# baseControl2.net
KiCad netlist of a schematic drawn in Altium Designer
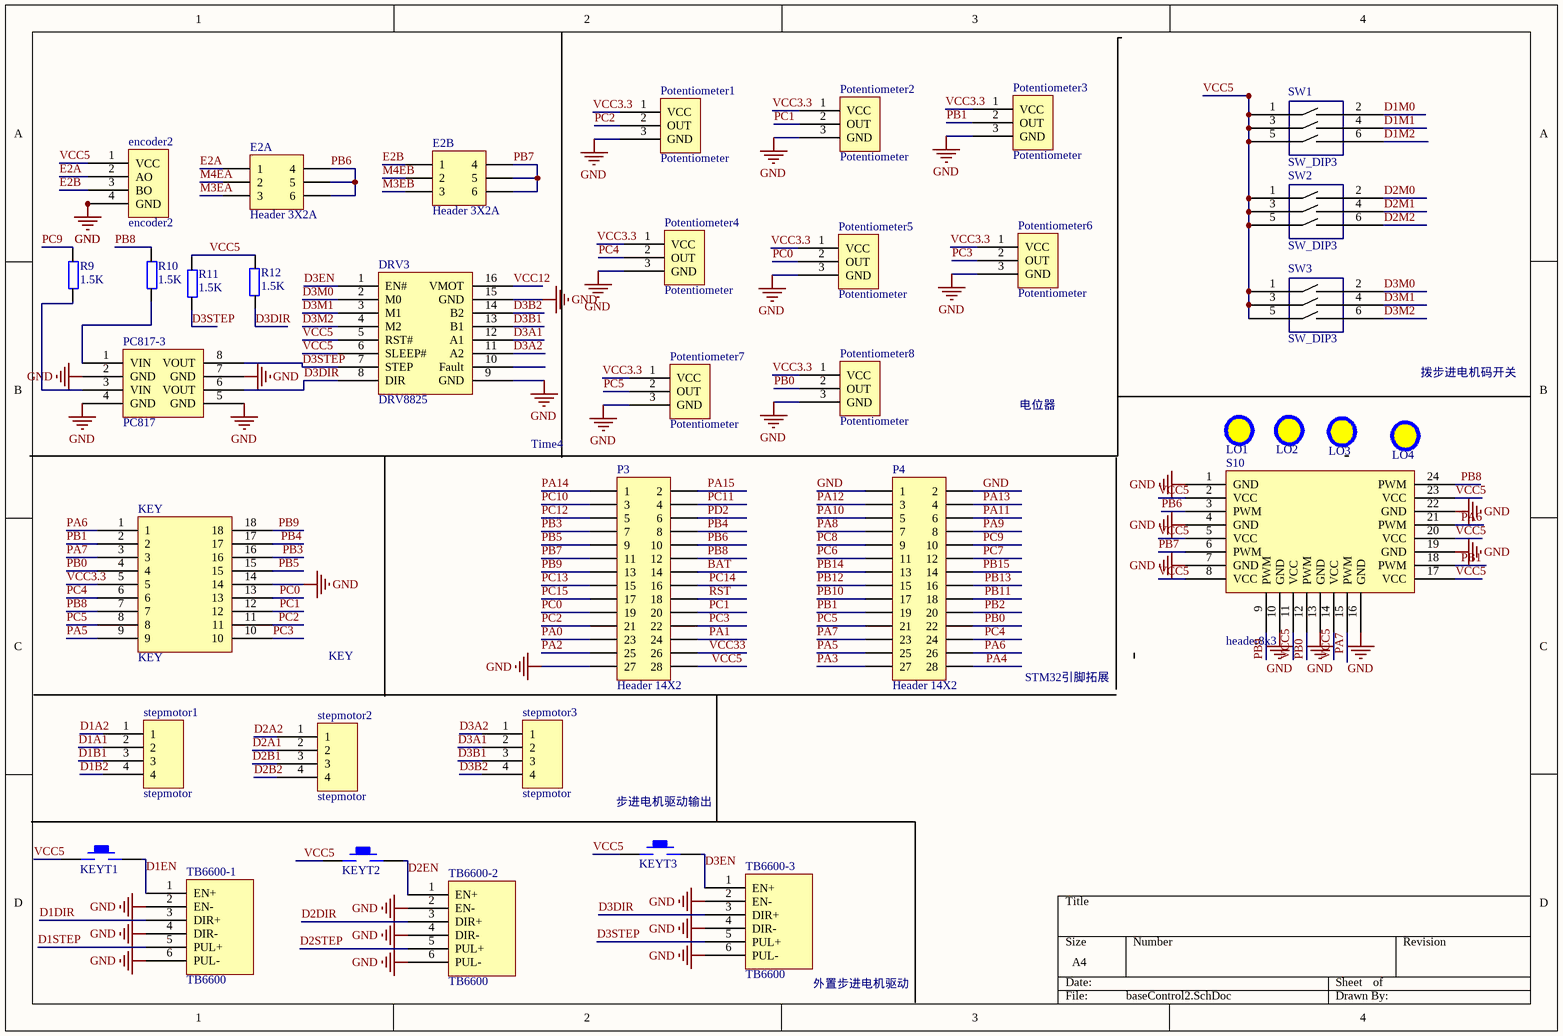
[diagram p0: baseControl2.SchDoc]

(export (version "E")
  (design (tool "Eeschema 10.0.6"))
  (components
    (comp (ref "DRV3")
      (value "DRV8825")
      (footprint "DRV8825")
      (libsource (lib "controlBsae") (part "DRV8825"))
    )
    (comp (ref "E2A")
      (value "Header 3X2A")
      (footprint "HDR2X3_CEN")
      (description "Header, 3-Pin, Dual row")
      (fields (field (name "PUBLISHER") "Altium Limited"))
      (libsource (lib "Miscellaneous Connectors") (part "Header 3X2A"))
    )
    (comp (ref "E2B")
      (value "Header 3X2A")
      (footprint "HDR2X3_CEN")
      (description "Header, 3-Pin, Dual row")
      (fields (field (name "PUBLISHER") "Altium Limited"))
      (libsource (lib "Miscellaneous Connectors") (part "Header 3X2A"))
    )
    (comp (ref "encoder2")
      (value "encoder2")
      (footprint "XH-4-254")
      (libsource (lib "controlBsae") (part "encoder"))
    )
    (comp (ref "KEY") (value "KEY") (footprint "KEY") (libsource (lib "controlBsae") (part "KEY")))
    (comp (ref "KEYT1") (value "KEY") (footprint "KEY_M") (libsource (lib "CORE") (part "KEY")))
    (comp (ref "KEYT2") (value "KEY") (footprint "KEY_M") (libsource (lib "CORE") (part "KEY")))
    (comp (ref "KEYT3") (value "KEY") (footprint "KEY_M") (libsource (lib "CORE") (part "KEY")))
    (comp (ref "LO1") (value "螺丝孔") (footprint "VIA") (libsource (lib "CORE") (part "螺丝孔")))
    (comp (ref "LO2") (value "螺丝孔") (footprint "VIA") (libsource (lib "CORE") (part "螺丝孔")))
    (comp (ref "LO3") (value "螺丝孔") (footprint "VIA") (libsource (lib "CORE") (part "螺丝孔")))
    (comp (ref "LO4") (value "螺丝孔") (footprint "VIA") (libsource (lib "CORE") (part "螺丝孔")))
    (comp (ref "P3")
      (value "Header 14X2")
      (footprint "HDR2X14")
      (description "Header, 14-Pin, Dual row")
      (fields (field (name "PUBLISHER") "Altium Limited"))
      (libsource (lib "Miscellaneous Connectors") (part "Header 14X2"))
    )
    (comp (ref "P4")
      (value "Header 14X2")
      (footprint "HDR2X14")
      (description "Header, 14-Pin, Dual row")
      (fields (field (name "PUBLISHER") "Altium Limited"))
      (libsource (lib "Miscellaneous Connectors") (part "Header 14X2"))
    )
    (comp (ref "PC817-3") (value "PC817") (footprint "DIP4") (libsource (lib "controlBsae") (part "PC817")))
    (comp (ref "Potentiometer1")
      (value "Potentiometer")
      (footprint "Potentiometer")
      (libsource (lib "controlBsae") (part "Potentiometer"))
    )
    (comp (ref "Potentiometer2")
      (value "Potentiometer")
      (footprint "Potentiometer")
      (libsource (lib "controlBsae") (part "Potentiometer"))
    )
    (comp (ref "Potentiometer3")
      (value "Potentiometer")
      (footprint "Potentiometer")
      (libsource (lib "controlBsae") (part "Potentiometer"))
    )
    (comp (ref "Potentiometer4")
      (value "Potentiometer")
      (footprint "Potentiometer")
      (libsource (lib "controlBsae") (part "Potentiometer"))
    )
    (comp (ref "Potentiometer5")
      (value "Potentiometer")
      (footprint "Potentiometer")
      (libsource (lib "controlBsae") (part "Potentiometer"))
    )
    (comp (ref "Potentiometer6")
      (value "Potentiometer")
      (footprint "Potentiometer")
      (libsource (lib "controlBsae") (part "Potentiometer"))
    )
    (comp (ref "Potentiometer7")
      (value "Potentiometer")
      (footprint "Potentiometer")
      (libsource (lib "controlBsae") (part "Potentiometer"))
    )
    (comp (ref "Potentiometer8")
      (value "Potentiometer")
      (footprint "Potentiometer")
      (libsource (lib "controlBsae") (part "Potentiometer"))
    )
    (comp (ref "R9") (value "1.5K") (footprint "0603P") (libsource (lib "CORE") (part "R")))
    (comp (ref "R10") (value "1.5K") (footprint "0603P") (libsource (lib "CORE") (part "R")))
    (comp (ref "R11") (value "1.5K") (footprint "0603P") (libsource (lib "CORE") (part "R")))
    (comp (ref "R12") (value "1.5K") (footprint "0603P") (libsource (lib "CORE") (part "R")))
    (comp (ref "S10")
      (value "header8x3")
      (footprint "header8X3")
      (libsource (lib "baseControl") (part "header8x3"))
    )
    (comp (ref "stepmotor1")
      (value "stepmotor")
      (footprint "XH-4-254")
      (libsource (lib "controlBsae") (part "stepmotor"))
    )
    (comp (ref "stepmotor2")
      (value "stepmotor")
      (footprint "XH-4-254")
      (libsource (lib "controlBsae") (part "stepmotor"))
    )
    (comp (ref "stepmotor3")
      (value "stepmotor")
      (footprint "XH-4-254")
      (libsource (lib "controlBsae") (part "stepmotor"))
    )
    (comp (ref "SW1")
      (value "SW_DIP3")
      (footprint "SW_DIP3")
      (libsource (lib "controlBsae") (part "SW_DIP3"))
    )
    (comp (ref "SW2")
      (value "SW_DIP3")
      (footprint "SW_DIP3")
      (libsource (lib "controlBsae") (part "SW_DIP3"))
    )
    (comp (ref "SW3")
      (value "SW_DIP3")
      (footprint "SW_DIP3")
      (libsource (lib "controlBsae") (part "SW_DIP3"))
    )
    (comp (ref "TB6600-1")
      (value "TB6600")
      (footprint "XH-6-254")
      (libsource (lib "controlBsae") (part "TB6600"))
    )
    (comp (ref "TB6600-2")
      (value "TB6600")
      (footprint "XH-6-254")
      (libsource (lib "controlBsae") (part "TB6600"))
    )
    (comp (ref "TB6600-3")
      (value "TB6600")
      (footprint "XH-6-254")
      (libsource (lib "controlBsae") (part "TB6600"))
    )
  )
  (nets
    (net (code "1") (name "/BAT") (class "Default")
      (node (ref "P3") (pin "14") (pinfunction "14_14") (pintype "passive"))
    )
    (net (code "2") (name "/D1A1") (class "Default")
      (node (ref "stepmotor1") (pin "2") (pinfunction "2_2") (pintype "passive"))
    )
    (net (code "3") (name "/D1A2") (class "Default")
      (node (ref "stepmotor1") (pin "1") (pinfunction "1_1") (pintype "passive"))
    )
    (net (code "4") (name "/D1B1") (class "Default")
      (node (ref "stepmotor1") (pin "3") (pinfunction "3_3") (pintype "passive"))
    )
    (net (code "5") (name "/D1B2") (class "Default")
      (node (ref "stepmotor1") (pin "4") (pinfunction "4_4") (pintype "passive"))
    )
    (net (code "6") (name "/D1DIR") (class "Default")
      (node (ref "TB6600-1") (pin "3") (pinfunction "DIR+_3") (pintype "passive"))
    )
    (net (code "7") (name "/D1EN") (class "Default")
      (node (ref "KEYT1") (pin "2") (pinfunction "2_2") (pintype "passive"))
      (node (ref "TB6600-1") (pin "1") (pinfunction "EN+_1") (pintype "passive"))
    )
    (net (code "8") (name "/D1M0") (class "Default")
      (node (ref "SW1") (pin "2") (pinfunction "2_2") (pintype "passive"))
    )
    (net (code "9") (name "/D1M1") (class "Default")
      (node (ref "SW1") (pin "4") (pinfunction "4_4") (pintype "passive"))
    )
    (net (code "10") (name "/D1M2") (class "Default")
      (node (ref "SW1") (pin "6") (pinfunction "6_6") (pintype "passive"))
    )
    (net (code "11") (name "/D1STEP") (class "Default")
      (node (ref "TB6600-1") (pin "5") (pinfunction "PUL+_5") (pintype "passive"))
    )
    (net (code "12") (name "/D2A1") (class "Default")
      (node (ref "stepmotor2") (pin "2") (pinfunction "2_2") (pintype "passive"))
    )
    (net (code "13") (name "/D2A2") (class "Default")
      (node (ref "stepmotor2") (pin "1") (pinfunction "1_1") (pintype "passive"))
    )
    (net (code "14") (name "/D2B1") (class "Default")
      (node (ref "stepmotor2") (pin "3") (pinfunction "3_3") (pintype "passive"))
    )
    (net (code "15") (name "/D2B2") (class "Default")
      (node (ref "stepmotor2") (pin "4") (pinfunction "4_4") (pintype "passive"))
    )
    (net (code "16") (name "/D2DIR") (class "Default")
      (node (ref "TB6600-2") (pin "3") (pinfunction "DIR+_3") (pintype "passive"))
    )
    (net (code "17") (name "/D2EN") (class "Default")
      (node (ref "KEYT2") (pin "2") (pinfunction "2_2") (pintype "passive"))
      (node (ref "TB6600-2") (pin "1") (pinfunction "EN+_1") (pintype "passive"))
    )
    (net (code "18") (name "/D2M0") (class "Default")
      (node (ref "SW2") (pin "2") (pinfunction "2_2") (pintype "passive"))
    )
    (net (code "19") (name "/D2M1") (class "Default")
      (node (ref "SW2") (pin "4") (pinfunction "4_4") (pintype "passive"))
    )
    (net (code "20") (name "/D2M2") (class "Default")
      (node (ref "SW2") (pin "6") (pinfunction "6_6") (pintype "passive"))
    )
    (net (code "21") (name "/D2STEP") (class "Default")
      (node (ref "TB6600-2") (pin "5") (pinfunction "PUL+_5") (pintype "passive"))
    )
    (net (code "22") (name "/D3A1") (class "Default")
      (node (ref "DRV3") (pin "12") (pinfunction "A1_12") (pintype "passive"))
      (node (ref "stepmotor3") (pin "2") (pinfunction "2_2") (pintype "passive"))
    )
    (net (code "23") (name "/D3A2") (class "Default")
      (node (ref "DRV3") (pin "11") (pinfunction "A2_11") (pintype "passive"))
      (node (ref "stepmotor3") (pin "1") (pinfunction "1_1") (pintype "passive"))
    )
    (net (code "24") (name "/D3B1") (class "Default")
      (node (ref "DRV3") (pin "13") (pinfunction "B1_13") (pintype "passive"))
      (node (ref "stepmotor3") (pin "3") (pinfunction "3_3") (pintype "passive"))
    )
    (net (code "25") (name "/D3B2") (class "Default")
      (node (ref "DRV3") (pin "14") (pinfunction "B2_14") (pintype "passive"))
      (node (ref "stepmotor3") (pin "4") (pinfunction "4_4") (pintype "passive"))
    )
    (net (code "26") (name "/D3DIR") (class "Default")
      (node (ref "DRV3") (pin "8") (pinfunction "DIR_8") (pintype "passive"))
      (node (ref "PC817-3") (pin "6") (pinfunction "VOUT_6") (pintype "passive"))
      (node (ref "R12") (pin "2") (pintype "passive"))
      (node (ref "TB6600-3") (pin "3") (pinfunction "DIR+_3") (pintype "passive"))
    )
    (net (code "27") (name "/D3EN") (class "Default")
      (node (ref "DRV3") (pin "1") (pinfunction "EN#_1") (pintype "passive"))
      (node (ref "KEYT3") (pin "2") (pinfunction "2_2") (pintype "passive"))
      (node (ref "TB6600-3") (pin "1") (pinfunction "EN+_1") (pintype "passive"))
    )
    (net (code "28") (name "/D3M0") (class "Default")
      (node (ref "DRV3") (pin "2") (pinfunction "M0_2") (pintype "passive"))
      (node (ref "SW3") (pin "2") (pinfunction "2_2") (pintype "passive"))
    )
    (net (code "29") (name "/D3M1") (class "Default")
      (node (ref "DRV3") (pin "3") (pinfunction "M1_3") (pintype "passive"))
      (node (ref "SW3") (pin "4") (pinfunction "4_4") (pintype "passive"))
    )
    (net (code "30") (name "/D3M2") (class "Default")
      (node (ref "DRV3") (pin "4") (pinfunction "M2_4") (pintype "passive"))
      (node (ref "SW3") (pin "6") (pinfunction "6_6") (pintype "passive"))
    )
    (net (code "31") (name "/D3STEP") (class "Default")
      (node (ref "DRV3") (pin "7") (pinfunction "STEP_7") (pintype "passive"))
      (node (ref "PC817-3") (pin "8") (pinfunction "VOUT_8") (pintype "passive"))
      (node (ref "R11") (pin "1") (pintype "passive"))
      (node (ref "TB6600-3") (pin "5") (pinfunction "PUL+_5") (pintype "passive"))
    )
    (net (code "32") (name "/E2A") (class "Default")
      (node (ref "E2A") (pin "1") (pinfunction "1_1") (pintype "passive"))
      (node (ref "encoder2") (pin "2") (pinfunction "AO_2") (pintype "passive"))
    )
    (net (code "33") (name "/E2B") (class "Default")
      (node (ref "E2B") (pin "1") (pinfunction "1_1") (pintype "passive"))
      (node (ref "encoder2") (pin "3") (pinfunction "BO_3") (pintype "passive"))
    )
    (net (code "34") (name "/M3EA") (class "Default")
      (node (ref "E2A") (pin "3") (pinfunction "3_3") (pintype "passive"))
    )
    (net (code "35") (name "/M3EB") (class "Default")
      (node (ref "E2B") (pin "3") (pinfunction "3_3") (pintype "passive"))
    )
    (net (code "36") (name "/M4EA") (class "Default")
      (node (ref "E2A") (pin "2") (pinfunction "2_2") (pintype "passive"))
    )
    (net (code "37") (name "/M4EB") (class "Default")
      (node (ref "E2B") (pin "2") (pinfunction "2_2") (pintype "passive"))
    )
    (net (code "38") (name "/PA0") (class "Default")
      (node (ref "P3") (pin "23") (pinfunction "23_23") (pintype "passive"))
    )
    (net (code "39") (name "/PA1") (class "Default")
      (node (ref "P3") (pin "24") (pinfunction "24_24") (pintype "passive"))
    )
    (net (code "40") (name "/PA2") (class "Default")
      (node (ref "P3") (pin "25") (pinfunction "25_25") (pintype "passive"))
    )
    (net (code "41") (name "/PA3") (class "Default")
      (node (ref "P4") (pin "27") (pinfunction "27_27") (pintype "passive"))
    )
    (net (code "42") (name "/PA4") (class "Default")
      (node (ref "P4") (pin "28") (pinfunction "28_28") (pintype "passive"))
    )
    (net (code "43") (name "/PA5") (class "Default")
      (node (ref "KEY") (pin "9") (pinfunction "9_9") (pintype "passive"))
      (node (ref "P4") (pin "25") (pinfunction "25_25") (pintype "passive"))
    )
    (net (code "44") (name "/PA6") (class "Default")
      (node (ref "KEY") (pin "1") (pinfunction "1_1") (pintype "passive"))
      (node (ref "P4") (pin "26") (pinfunction "26_26") (pintype "passive"))
      (node (ref "S10") (pin "21") (pinfunction "PWM_21") (pintype "passive"))
    )
    (net (code "45") (name "/PA7") (class "Default")
      (node (ref "KEY") (pin "3") (pinfunction "3_3") (pintype "passive"))
      (node (ref "P4") (pin "23") (pinfunction "23_23") (pintype "passive"))
      (node (ref "S10") (pin "15") (pinfunction "PWM_15") (pintype "passive"))
    )
    (net (code "46") (name "/PA8") (class "Default")
      (node (ref "P4") (pin "7") (pinfunction "7_7") (pintype "passive"))
    )
    (net (code "47") (name "/PA9") (class "Default")
      (node (ref "P4") (pin "8") (pinfunction "8_8") (pintype "passive"))
    )
    (net (code "48") (name "/PA10") (class "Default")
      (node (ref "P4") (pin "5") (pinfunction "5_5") (pintype "passive"))
    )
    (net (code "49") (name "/PA11") (class "Default")
      (node (ref "P4") (pin "6") (pinfunction "6_6") (pintype "passive"))
    )
    (net (code "50") (name "/PA12") (class "Default")
      (node (ref "P4") (pin "3") (pinfunction "3_3") (pintype "passive"))
    )
    (net (code "51") (name "/PA13") (class "Default")
      (node (ref "P4") (pin "4") (pinfunction "4_4") (pintype "passive"))
    )
    (net (code "52") (name "/PA14") (class "Default")
      (node (ref "P3") (pin "1") (pinfunction "1_1") (pintype "passive"))
    )
    (net (code "53") (name "/PA15") (class "Default")
      (node (ref "P3") (pin "2") (pinfunction "2_2") (pintype "passive"))
    )
    (net (code "54") (name "/PB0") (class "Default")
      (node (ref "KEY") (pin "4") (pinfunction "4_4") (pintype "passive"))
      (node (ref "P4") (pin "22") (pinfunction "22_22") (pintype "passive"))
      (node (ref "Potentiometer8") (pin "2") (pinfunction "OUT_2") (pintype "passive"))
      (node (ref "S10") (pin "12") (pinfunction "PWM_12") (pintype "passive"))
    )
    (net (code "55") (name "/PB1") (class "Default")
      (node (ref "KEY") (pin "2") (pinfunction "2_2") (pintype "passive"))
      (node (ref "P4") (pin "19") (pinfunction "19_19") (pintype "passive"))
      (node (ref "Potentiometer3") (pin "2") (pinfunction "OUT_2") (pintype "passive"))
      (node (ref "S10") (pin "18") (pinfunction "PWM_18") (pintype "passive"))
    )
    (net (code "56") (name "/PB2") (class "Default")
      (node (ref "P4") (pin "20") (pinfunction "20_20") (pintype "passive"))
    )
    (net (code "57") (name "/PB3") (class "Default")
      (node (ref "KEY") (pin "16") (pinfunction "16_16") (pintype "passive"))
      (node (ref "P3") (pin "7") (pinfunction "7_7") (pintype "passive"))
    )
    (net (code "58") (name "/PB4") (class "Default")
      (node (ref "KEY") (pin "17") (pinfunction "17_17") (pintype "passive"))
      (node (ref "P3") (pin "8") (pinfunction "8_8") (pintype "passive"))
    )
    (net (code "59") (name "/PB5") (class "Default")
      (node (ref "KEY") (pin "15") (pinfunction "15_15") (pintype "passive"))
      (node (ref "P3") (pin "9") (pinfunction "9_9") (pintype "passive"))
    )
    (net (code "60") (name "/PB6") (class "Default")
      (node (ref "E2A") (pin "4") (pinfunction "4_4") (pintype "passive"))
      (node (ref "E2A") (pin "5") (pinfunction "5_5") (pintype "passive"))
      (node (ref "E2A") (pin "6") (pinfunction "6_6") (pintype "passive"))
      (node (ref "P3") (pin "10") (pinfunction "10_10") (pintype "passive"))
      (node (ref "S10") (pin "3") (pinfunction "PWM_3") (pintype "passive"))
    )
    (net (code "61") (name "/PB7") (class "Default")
      (node (ref "E2B") (pin "4") (pinfunction "4_4") (pintype "passive"))
      (node (ref "E2B") (pin "5") (pinfunction "5_5") (pintype "passive"))
      (node (ref "E2B") (pin "6") (pinfunction "6_6") (pintype "passive"))
      (node (ref "P3") (pin "11") (pinfunction "11_11") (pintype "passive"))
      (node (ref "S10") (pin "6") (pinfunction "PWM_6") (pintype "passive"))
    )
    (net (code "62") (name "/PB8") (class "Default")
      (node (ref "KEY") (pin "7") (pinfunction "7_7") (pintype "passive"))
      (node (ref "P3") (pin "12") (pinfunction "12_12") (pintype "passive"))
      (node (ref "R10") (pin "2") (pintype "passive"))
      (node (ref "S10") (pin "24") (pinfunction "PWM_24") (pintype "passive"))
    )
    (net (code "63") (name "/PB9") (class "Default")
      (node (ref "KEY") (pin "18") (pinfunction "18_18") (pintype "passive"))
      (node (ref "P3") (pin "13") (pinfunction "13_13") (pintype "passive"))
      (node (ref "S10") (pin "9") (pinfunction "PWM_9") (pintype "passive"))
    )
    (net (code "64") (name "/PB10") (class "Default")
      (node (ref "P4") (pin "17") (pinfunction "17_17") (pintype "passive"))
    )
    (net (code "65") (name "/PB11") (class "Default")
      (node (ref "P4") (pin "18") (pinfunction "18_18") (pintype "passive"))
    )
    (net (code "66") (name "/PB12") (class "Default")
      (node (ref "P4") (pin "15") (pinfunction "15_15") (pintype "passive"))
    )
    (net (code "67") (name "/PB13") (class "Default")
      (node (ref "P4") (pin "16") (pinfunction "16_16") (pintype "passive"))
    )
    (net (code "68") (name "/PB14") (class "Default")
      (node (ref "P4") (pin "13") (pinfunction "13_13") (pintype "passive"))
    )
    (net (code "69") (name "/PB15") (class "Default")
      (node (ref "P4") (pin "14") (pinfunction "14_14") (pintype "passive"))
    )
    (net (code "70") (name "/PC0") (class "Default")
      (node (ref "KEY") (pin "13") (pinfunction "13_13") (pintype "passive"))
      (node (ref "P3") (pin "19") (pinfunction "19_19") (pintype "passive"))
      (node (ref "Potentiometer5") (pin "2") (pinfunction "OUT_2") (pintype "passive"))
    )
    (net (code "71") (name "/PC1") (class "Default")
      (node (ref "KEY") (pin "12") (pinfunction "12_12") (pintype "passive"))
      (node (ref "P3") (pin "20") (pinfunction "20_20") (pintype "passive"))
      (node (ref "Potentiometer2") (pin "2") (pinfunction "OUT_2") (pintype "passive"))
    )
    (net (code "72") (name "/PC2") (class "Default")
      (node (ref "KEY") (pin "11") (pinfunction "11_11") (pintype "passive"))
      (node (ref "P3") (pin "21") (pinfunction "21_21") (pintype "passive"))
      (node (ref "Potentiometer1") (pin "2") (pinfunction "OUT_2") (pintype "passive"))
    )
    (net (code "73") (name "/PC3") (class "Default")
      (node (ref "KEY") (pin "10") (pinfunction "10_10") (pintype "passive"))
      (node (ref "P3") (pin "22") (pinfunction "22_22") (pintype "passive"))
      (node (ref "Potentiometer6") (pin "2") (pinfunction "OUT_2") (pintype "passive"))
    )
    (net (code "74") (name "/PC4") (class "Default")
      (node (ref "KEY") (pin "6") (pinfunction "6_6") (pintype "passive"))
      (node (ref "P4") (pin "24") (pinfunction "24_24") (pintype "passive"))
      (node (ref "Potentiometer4") (pin "2") (pinfunction "OUT_2") (pintype "passive"))
    )
    (net (code "75") (name "/PC5") (class "Default")
      (node (ref "KEY") (pin "8") (pinfunction "8_8") (pintype "passive"))
      (node (ref "P4") (pin "21") (pinfunction "21_21") (pintype "passive"))
      (node (ref "Potentiometer7") (pin "2") (pinfunction "OUT_2") (pintype "passive"))
    )
    (net (code "76") (name "/PC6") (class "Default")
      (node (ref "P4") (pin "11") (pinfunction "11_11") (pintype "passive"))
    )
    (net (code "77") (name "/PC7") (class "Default")
      (node (ref "P4") (pin "12") (pinfunction "12_12") (pintype "passive"))
    )
    (net (code "78") (name "/PC8") (class "Default")
      (node (ref "P4") (pin "9") (pinfunction "9_9") (pintype "passive"))
    )
    (net (code "79") (name "/PC9") (class "Default")
      (node (ref "P4") (pin "10") (pinfunction "10_10") (pintype "passive"))
      (node (ref "R9") (pin "2") (pintype "passive"))
    )
    (net (code "80") (name "/PC10") (class "Default")
      (node (ref "P3") (pin "3") (pinfunction "3_3") (pintype "passive"))
    )
    (net (code "81") (name "/PC11") (class "Default")
      (node (ref "P3") (pin "4") (pinfunction "4_4") (pintype "passive"))
    )
    (net (code "82") (name "/PC12") (class "Default")
      (node (ref "P3") (pin "5") (pinfunction "5_5") (pintype "passive"))
    )
    (net (code "83") (name "/PC13") (class "Default")
      (node (ref "P3") (pin "15") (pinfunction "15_15") (pintype "passive"))
    )
    (net (code "84") (name "/PC14") (class "Default")
      (node (ref "P3") (pin "16") (pinfunction "16_16") (pintype "passive"))
    )
    (net (code "85") (name "/PC15") (class "Default")
      (node (ref "P3") (pin "17") (pinfunction "17_17") (pintype "passive"))
    )
    (net (code "86") (name "/PD2") (class "Default")
      (node (ref "P3") (pin "6") (pinfunction "6_6") (pintype "passive"))
    )
    (net (code "87") (name "/RST") (class "Default")
      (node (ref "P3") (pin "18") (pinfunction "18_18") (pintype "passive"))
    )
    (net (code "88") (name "/VCC3.3") (class "Default")
      (node (ref "KEY") (pin "5") (pinfunction "5_5") (pintype "passive"))
      (node (ref "Potentiometer1") (pin "1") (pinfunction "VCC_1") (pintype "passive"))
      (node (ref "Potentiometer2") (pin "1") (pinfunction "VCC_1") (pintype "passive"))
      (node (ref "Potentiometer3") (pin "1") (pinfunction "VCC_1") (pintype "passive"))
      (node (ref "Potentiometer4") (pin "1") (pinfunction "VCC_1") (pintype "passive"))
      (node (ref "Potentiometer5") (pin "1") (pinfunction "VCC_1") (pintype "passive"))
      (node (ref "Potentiometer6") (pin "1") (pinfunction "VCC_1") (pintype "passive"))
      (node (ref "Potentiometer7") (pin "1") (pinfunction "VCC_1") (pintype "passive"))
      (node (ref "Potentiometer8") (pin "1") (pinfunction "VCC_1") (pintype "passive"))
    )
    (net (code "89") (name "/VCC5") (class "Default")
      (node (ref "DRV3") (pin "5") (pinfunction "RST#_5") (pintype "passive"))
      (node (ref "DRV3") (pin "6") (pinfunction "SLEEP#_6") (pintype "passive"))
      (node (ref "KEYT1") (pin "1") (pinfunction "1_1") (pintype "passive"))
      (node (ref "KEYT2") (pin "1") (pinfunction "1_1") (pintype "passive"))
      (node (ref "KEYT3") (pin "1") (pinfunction "1_1") (pintype "passive"))
      (node (ref "P3") (pin "28") (pinfunction "28_28") (pintype "passive"))
      (node (ref "R11") (pin "2") (pintype "passive"))
      (node (ref "R12") (pin "1") (pintype "passive"))
      (node (ref "S10") (pin "11") (pinfunction "VCC_11") (pintype "passive"))
      (node (ref "S10") (pin "14") (pinfunction "VCC_14") (pintype "passive"))
      (node (ref "S10") (pin "17") (pinfunction "VCC_17") (pintype "passive"))
      (node (ref "S10") (pin "2") (pinfunction "VCC_2") (pintype "passive"))
      (node (ref "S10") (pin "20") (pinfunction "VCC_20") (pintype "passive"))
      (node (ref "S10") (pin "23") (pinfunction "VCC_23") (pintype "passive"))
      (node (ref "S10") (pin "5") (pinfunction "VCC_5") (pintype "passive"))
      (node (ref "S10") (pin "8") (pinfunction "VCC_8") (pintype "passive"))
      (node (ref "SW1") (pin "1") (pinfunction "1_1") (pintype "passive"))
      (node (ref "SW1") (pin "3") (pinfunction "3_3") (pintype "passive"))
      (node (ref "SW1") (pin "5") (pinfunction "5_5") (pintype "passive"))
      (node (ref "SW2") (pin "1") (pinfunction "1_1") (pintype "passive"))
      (node (ref "SW2") (pin "3") (pinfunction "3_3") (pintype "passive"))
      (node (ref "SW2") (pin "5") (pinfunction "5_5") (pintype "passive"))
      (node (ref "SW3") (pin "1") (pinfunction "1_1") (pintype "passive"))
      (node (ref "SW3") (pin "3") (pinfunction "3_3") (pintype "passive"))
      (node (ref "SW3") (pin "5") (pinfunction "5_5") (pintype "passive"))
      (node (ref "encoder2") (pin "1") (pinfunction "VCC_1") (pintype "passive"))
    )
    (net (code "90") (name "/VCC12") (class "Default")
      (node (ref "DRV3") (pin "16") (pinfunction "VMOT_16") (pintype "passive"))
    )
    (net (code "91") (name "/VCC33") (class "Default")
      (node (ref "P3") (pin "26") (pinfunction "26_26") (pintype "passive"))
    )
    (net (code "92") (name "GND") (class "Default")
      (node (ref "DRV3") (pin "15") (pinfunction "GND_15") (pintype "passive"))
      (node (ref "DRV3") (pin "9") (pinfunction "GND_9") (pintype "passive"))
      (node (ref "KEY") (pin "14") (pinfunction "14_14") (pintype "passive"))
      (node (ref "P3") (pin "27") (pinfunction "27_27") (pintype "passive"))
      (node (ref "P4") (pin "1") (pinfunction "1_1") (pintype "passive"))
      (node (ref "P4") (pin "2") (pinfunction "2_2") (pintype "passive"))
      (node (ref "PC817-3") (pin "2") (pinfunction "GND_2") (pintype "passive"))
      (node (ref "PC817-3") (pin "4") (pinfunction "GND_4") (pintype "passive"))
      (node (ref "PC817-3") (pin "5") (pinfunction "GND_5") (pintype "passive"))
      (node (ref "PC817-3") (pin "7") (pinfunction "GND_7") (pintype "passive"))
      (node (ref "Potentiometer1") (pin "3") (pinfunction "GND_3") (pintype "passive"))
      (node (ref "Potentiometer2") (pin "3") (pinfunction "GND_3") (pintype "passive"))
      (node (ref "Potentiometer3") (pin "3") (pinfunction "GND_3") (pintype "passive"))
      (node (ref "Potentiometer4") (pin "3") (pinfunction "GND_3") (pintype "passive"))
      (node (ref "Potentiometer5") (pin "3") (pinfunction "GND_3") (pintype "passive"))
      (node (ref "Potentiometer6") (pin "3") (pinfunction "GND_3") (pintype "passive"))
      (node (ref "Potentiometer7") (pin "3") (pinfunction "GND_3") (pintype "passive"))
      (node (ref "Potentiometer8") (pin "3") (pinfunction "GND_3") (pintype "passive"))
      (node (ref "S10") (pin "1") (pinfunction "GND_1") (pintype "passive"))
      (node (ref "S10") (pin "10") (pinfunction "GND_10") (pintype "passive"))
      (node (ref "S10") (pin "13") (pinfunction "GND_13") (pintype "passive"))
      (node (ref "S10") (pin "16") (pinfunction "GND_16") (pintype "passive"))
      (node (ref "S10") (pin "19") (pinfunction "GND_19") (pintype "passive"))
      (node (ref "S10") (pin "22") (pinfunction "GND_22") (pintype "passive"))
      (node (ref "S10") (pin "4") (pinfunction "GND_4") (pintype "passive"))
      (node (ref "S10") (pin "7") (pinfunction "GND_7") (pintype "passive"))
      (node (ref "TB6600-1") (pin "2") (pinfunction "EN-_2") (pintype "passive"))
      (node (ref "TB6600-1") (pin "4") (pinfunction "DIR-_4") (pintype "passive"))
      (node (ref "TB6600-1") (pin "6") (pinfunction "PUL-_6") (pintype "passive"))
      (node (ref "TB6600-2") (pin "2") (pinfunction "EN-_2") (pintype "passive"))
      (node (ref "TB6600-2") (pin "4") (pinfunction "DIR-_4") (pintype "passive"))
      (node (ref "TB6600-2") (pin "6") (pinfunction "PUL-_6") (pintype "passive"))
      (node (ref "TB6600-3") (pin "2") (pinfunction "EN-_2") (pintype "passive"))
      (node (ref "TB6600-3") (pin "4") (pinfunction "DIR-_4") (pintype "passive"))
      (node (ref "TB6600-3") (pin "6") (pinfunction "PUL-_6") (pintype "passive"))
      (node (ref "encoder2") (pin "4") (pinfunction "GND_4") (pintype "passive"))
    )
    (net (code "93") (name "Net-(PC817-3-VIN-Pad1)") (class "Default")
      (node (ref "PC817-3") (pin "1") (pinfunction "VIN_1") (pintype "passive"))
      (node (ref "R10") (pin "1") (pintype "passive"))
    )
    (net (code "94") (name "Net-(PC817-3-VIN-Pad3)") (class "Default")
      (node (ref "PC817-3") (pin "3") (pinfunction "VIN_3") (pintype "passive"))
      (node (ref "R9") (pin "1") (pintype "passive"))
    )
    (net (code "95") (name "unconnected-(DRV3-Fault-Pad10)") (class "Default")
      (node (ref "DRV3") (pin "10") (pinfunction "Fault_10") (pintype "passive"))
    )
  )
)
